# XXXX_426471_007_Secondary_PCB_Raspberry_.net
KiCad netlist of a schematic drawn in Altium Designer
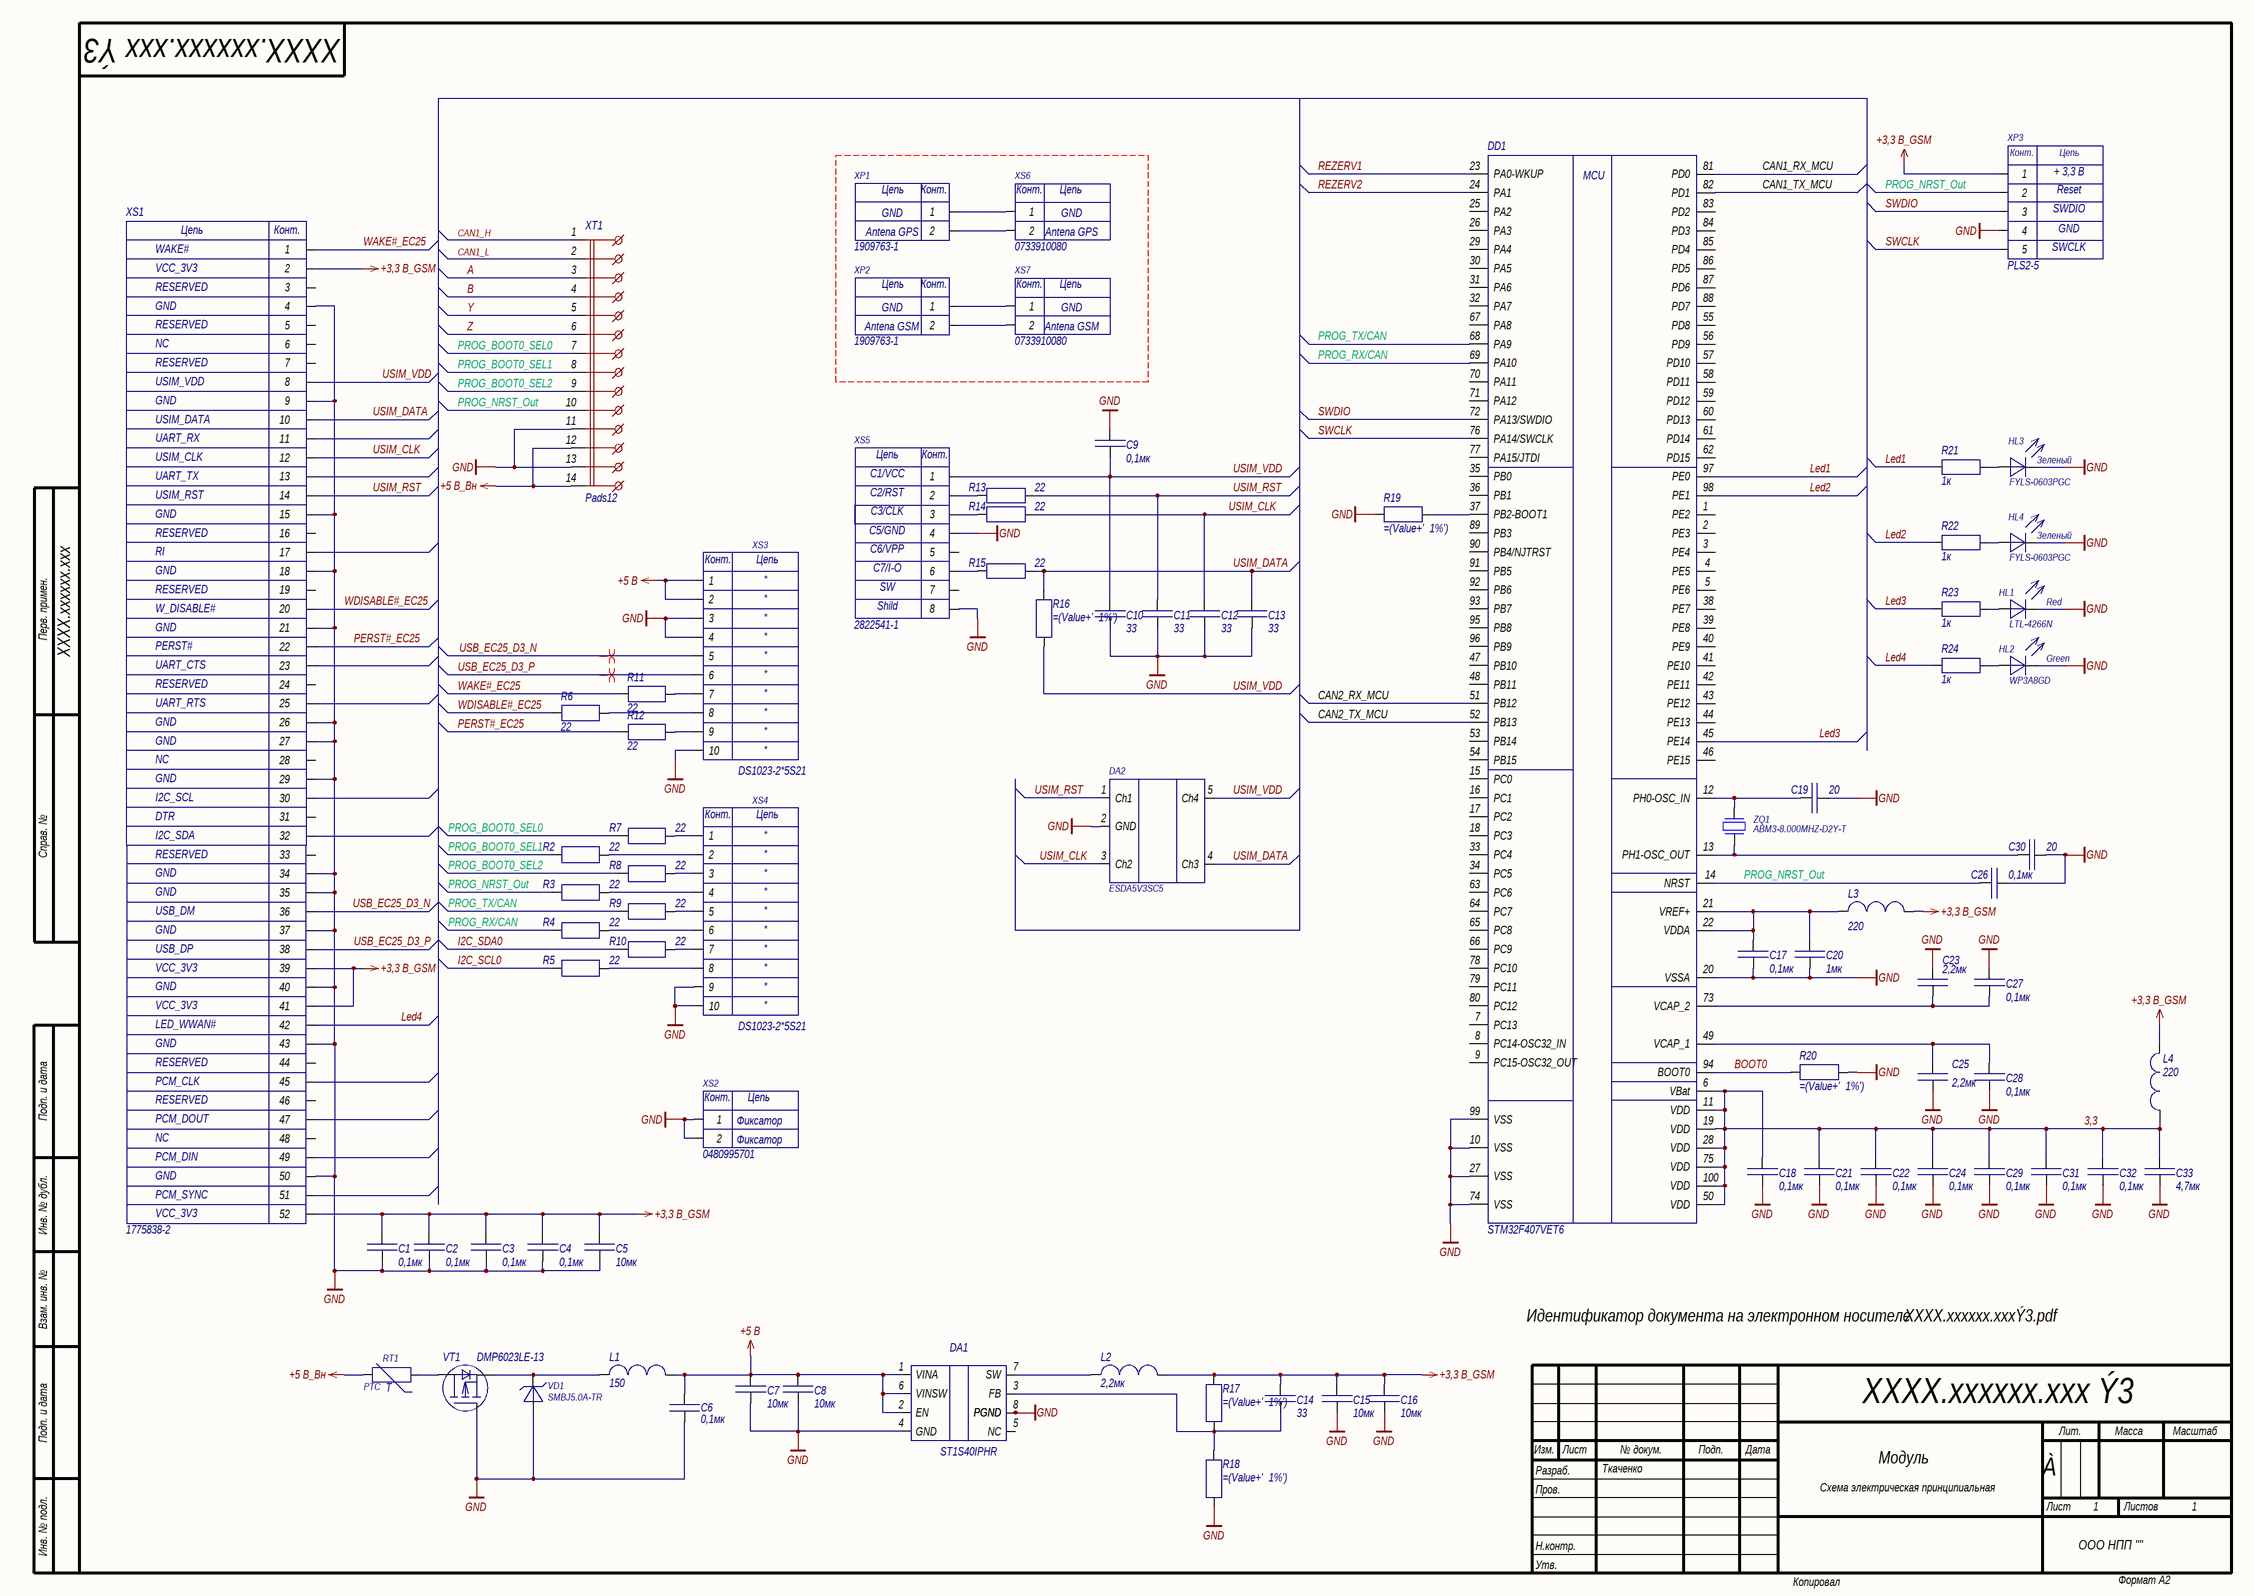
[diagram p0: XXXX.426471.007 Secondary_PCB_Raspberry_List1.SchDoc]

(export (version "E")
  (design (tool "Eeschema 10.0.6"))
  (components
    (comp (ref "C1")
      (value "0,1мк")
      (footprint "CAPC1608N_SL")
      (description "CAP CER 0.1UF 50V 10% X7R 0603")
      (fields
        (field (name "PARTNUMBER") "CC0603KRX7R9BB104_Yageo")
        (field (name "MANUFACTURER") "Yageo")
        (field (name "АВТОР") "Хоменко С.П.")
      )
      (libsource (lib "BaseContactmodul") (part "C_CER"))
    )
    (comp (ref "C2")
      (value "0,1мк")
      (footprint "CAPC1608N_SL")
      (description "CAP CER 0.1UF 50V 10% X7R 0603")
      (fields
        (field (name "PARTNUMBER") "CC0603KRX7R9BB104_Yageo")
        (field (name "MANUFACTURER") "Yageo")
        (field (name "АВТОР") "Хоменко С.П.")
      )
      (libsource (lib "BaseContactmodul") (part "C_CER"))
    )
    (comp (ref "C3")
      (value "0,1мк")
      (footprint "CAPC1608N_SL")
      (description "CAP CER 0.1UF 50V 10% X7R 0603")
      (fields
        (field (name "PARTNUMBER") "CC0603KRX7R9BB104_Yageo")
        (field (name "MANUFACTURER") "Yageo")
        (field (name "АВТОР") "Хоменко С.П.")
      )
      (libsource (lib "BaseContactmodul") (part "C_CER"))
    )
    (comp (ref "C4")
      (value "0,1мк")
      (footprint "CAPC1608N_SL")
      (description "CAP CER 0.1UF 50V 10% X7R 0603")
      (fields
        (field (name "PARTNUMBER") "CC0603KRX7R9BB104_Yageo")
        (field (name "MANUFACTURER") "Yageo")
        (field (name "АВТОР") "Хоменко С.П.")
      )
      (libsource (lib "BaseContactmodul") (part "C_CER"))
    )
    (comp (ref "C5")
      (value "10мк")
      (footprint "CAPC2012N")
      (description "CAP CER 10UF 10V 10% X7R 0805")
      (fields
        (field (name "PARTNUMBER") "GCM21BR71A106KE22L_Murata Electronics")
        (field (name "MANUFACTURER") "Murata Electronics")
        (field (name "АВТОР") "Хоменко С.П.")
      )
      (libsource (lib "BaseContactmodul") (part "C_CER"))
    )
    (comp (ref "C6")
      (value "0,1мк")
      (footprint "CAPC1608N_sl")
      (description "CAP CER 0.1UF 50V 10% X7R 0603")
      (fields
        (field (name "PARTNUMBER") "CC0603KRX7R9BB104_Yageo")
        (field (name "MANUFACTURER") "Yageo")
        (field (name "АВТОР") "Хоменко С.П.")
      )
      (libsource (lib "BaseContactmodul") (part "C_CER"))
    )
    (comp (ref "C7")
      (value "10мк")
      (footprint "CAPC2012N")
      (description "CAP CER 10UF 10V 10% X7R 0805")
      (fields
        (field (name "PARTNUMBER") "GCM21BR71A106KE22L_Murata Electronics")
        (field (name "MANUFACTURER") "Murata Electronics")
        (field (name "АВТОР") "Хоменко С.П.")
      )
      (libsource (lib "BaseContactmodul") (part "C_CER"))
    )
    (comp (ref "C8")
      (value "10мк")
      (footprint "CAPC2012N")
      (description "CAP CER 10UF 10V 10% X7R 0805")
      (fields
        (field (name "PARTNUMBER") "GCM21BR71A106KE22L_Murata Electronics")
        (field (name "MANUFACTURER") "Murata Electronics")
        (field (name "АВТОР") "Хоменко С.П.")
      )
      (libsource (lib "BaseContactmodul") (part "C_CER"))
    )
    (comp (ref "C9")
      (value "0,1мк")
      (footprint "CAPC1608N_SL")
      (description "CAP CER 0.1UF 50V 10% X7R 0603")
      (fields
        (field (name "PARTNUMBER") "CC0603KRX7R9BB104_Yageo")
        (field (name "MANUFACTURER") "Yageo")
        (field (name "АВТОР") "Хоменко С.П.")
      )
      (libsource (lib "BaseContactmodul") (part "C_CER"))
    )
    (comp (ref "C10")
      (value "33")
      (footprint "CAPC1608N_SL")
      (description "CAP CER 33PF 50V NPO 0603")
      (fields
        (field (name "PARTNUMBER") "CC0603JRNPO9BN330_Yageo")
        (field (name "MANUFACTURER") "Yageo")
        (field (name "АВТОР") "Хоменко С.П.")
      )
      (libsource (lib "BaseContactmodul") (part "C_CER"))
    )
    (comp (ref "C11")
      (value "33")
      (footprint "CAPC1608N_SL")
      (description "CAP CER 33PF 50V NPO 0603")
      (fields
        (field (name "PARTNUMBER") "CC0603JRNPO9BN330_Yageo")
        (field (name "MANUFACTURER") "Yageo")
        (field (name "АВТОР") "Хоменко С.П.")
      )
      (libsource (lib "BaseContactmodul") (part "C_CER"))
    )
    (comp (ref "C12")
      (value "33")
      (footprint "CAPC1608N_SL")
      (description "CAP CER 33PF 50V NPO 0603")
      (fields
        (field (name "PARTNUMBER") "CC0603JRNPO9BN330_Yageo")
        (field (name "MANUFACTURER") "Yageo")
        (field (name "АВТОР") "Хоменко С.П.")
      )
      (libsource (lib "BaseContactmodul") (part "C_CER"))
    )
    (comp (ref "C13")
      (value "33")
      (footprint "CAPC1608N_SL")
      (description "CAP CER 33PF 50V NPO 0603")
      (fields
        (field (name "PARTNUMBER") "CC0603JRNPO9BN330_Yageo")
        (field (name "MANUFACTURER") "Yageo")
        (field (name "АВТОР") "Хоменко С.П.")
      )
      (libsource (lib "BaseContactmodul") (part "C_CER"))
    )
    (comp (ref "C14")
      (value "33")
      (footprint "CAPC1608N_SL")
      (description "CAP CER 33PF 50V NPO 0603")
      (fields
        (field (name "PARTNUMBER") "CC0603JRNPO9BN330_Yageo")
        (field (name "MANUFACTURER") "Yageo")
        (field (name "АВТОР") "Хоменко С.П.")
      )
      (libsource (lib "BaseContactmodul") (part "C_CER"))
    )
    (comp (ref "C15")
      (value "10мк")
      (footprint "CAPC2012N")
      (description "CAP CER 10UF 10V 10% X7R 0805")
      (fields
        (field (name "PARTNUMBER") "GCM21BR71A106KE22L_Murata Electronics")
        (field (name "MANUFACTURER") "Murata Electronics")
        (field (name "АВТОР") "Хоменко С.П.")
      )
      (libsource (lib "BaseContactmodul") (part "C_CER"))
    )
    (comp (ref "C16")
      (value "10мк")
      (footprint "CAPC2012N")
      (description "CAP CER 10UF 10V 10% X7R 0805")
      (fields
        (field (name "PARTNUMBER") "GCM21BR71A106KE22L_Murata Electronics")
        (field (name "MANUFACTURER") "Murata Electronics")
        (field (name "АВТОР") "Хоменко С.П.")
      )
      (libsource (lib "BaseContactmodul") (part "C_CER"))
    )
    (comp (ref "C17")
      (value "0,1мк")
      (footprint "CAPC1608N_SL")
      (description "CAP CER 0.1UF 50V 10% X7R 0603")
      (fields
        (field (name "PARTNUMBER") "CC0603KRX7R9BB104_Yageo")
        (field (name "MANUFACTURER") "Yageo")
        (field (name "АВТОР") "Хоменко С.П.")
      )
      (libsource (lib "BaseContactmodul") (part "C_CER"))
    )
    (comp (ref "C18")
      (value "0,1мк")
      (footprint "CAPC1608N_SL")
      (description "CAP CER 0.1UF 50V 10% X7R 0603")
      (fields
        (field (name "PARTNUMBER") "CC0603KRX7R9BB104_Yageo")
        (field (name "MANUFACTURER") "Yageo")
        (field (name "АВТОР") "Хоменко С.П.")
      )
      (libsource (lib "BaseContactmodul") (part "C_CER"))
    )
    (comp (ref "C19")
      (value "20")
      (footprint "CAPC1608N_SL")
      (description "CAP CER 20PF 50V 5% NPO 0603")
      (fields
        (field (name "PARTNUMBER") "CC0603JRNPO9BN200_Yageo")
        (field (name "MANUFACTURER") "Yageo")
        (field (name "АВТОР") "Хоменко С.П.")
      )
      (libsource (lib "BaseContactmodul") (part "C_CER"))
    )
    (comp (ref "C20")
      (value "1мк")
      (footprint "CAPC1608N_SL")
      (description "CAP CER 1UF 16V 10% X7R 0603")
      (fields
        (field (name "PARTNUMBER") "CC0603KRX7R7BB105_Yageo")
        (field (name "MANUFACTURER") "Yageo")
        (field (name "АВТОР") "Хоменко С.П.")
      )
      (libsource (lib "BaseContactmodul") (part "C_CER"))
    )
    (comp (ref "C21")
      (value "0,1мк")
      (footprint "CAPC1608N_SL")
      (description "CAP CER 0.1UF 50V 10% X7R 0603")
      (fields
        (field (name "PARTNUMBER") "CC0603KRX7R9BB104_Yageo")
        (field (name "MANUFACTURER") "Yageo")
        (field (name "АВТОР") "Хоменко С.П.")
      )
      (libsource (lib "BaseContactmodul") (part "C_CER"))
    )
    (comp (ref "C22")
      (value "0,1мк")
      (footprint "CAPC1608N_SL")
      (description "CAP CER 0.1UF 50V 10% X7R 0603")
      (fields
        (field (name "PARTNUMBER") "CC0603KRX7R9BB104_Yageo")
        (field (name "MANUFACTURER") "Yageo")
        (field (name "АВТОР") "Хоменко С.П.")
      )
      (libsource (lib "BaseContactmodul") (part "C_CER"))
    )
    (comp (ref "C23")
      (value "2,2мк")
      (footprint "CAPC1608N_SL")
      (description "CAP CER 2.2UF 10V X7R 0603")
      (fields
        (field (name "PARTNUMBER") "GRM188R71A225KE15D_Murata Electronics")
        (field (name "MANUFACTURER") "Murata Electronics")
        (field (name "АВТОР") "Хоменко С.П.")
      )
      (libsource (lib "BaseContactmodul") (part "C_CER"))
    )
    (comp (ref "C24")
      (value "0,1мк")
      (footprint "CAPC1608N_SL")
      (description "CAP CER 0.1UF 50V 10% X7R 0603")
      (fields
        (field (name "PARTNUMBER") "CC0603KRX7R9BB104_Yageo")
        (field (name "MANUFACTURER") "Yageo")
        (field (name "АВТОР") "Хоменко С.П.")
      )
      (libsource (lib "BaseContactmodul") (part "C_CER"))
    )
    (comp (ref "C25")
      (value "2,2мк")
      (footprint "CAPC1608N_SL")
      (description "CAP CER 2.2UF 10V X7R 0603")
      (fields
        (field (name "PARTNUMBER") "GRM188R71A225KE15D_Murata Electronics")
        (field (name "MANUFACTURER") "Murata Electronics")
        (field (name "АВТОР") "Хоменко С.П.")
      )
      (libsource (lib "BaseContactmodul") (part "C_CER"))
    )
    (comp (ref "C26")
      (value "0,1мк")
      (footprint "CAPC1608N_SL")
      (description "CAP CER 0.1UF 50V 10% X7R 0603")
      (fields
        (field (name "PARTNUMBER") "CC0603KRX7R9BB104_Yageo")
        (field (name "MANUFACTURER") "Yageo")
        (field (name "АВТОР") "Хоменко С.П.")
      )
      (libsource (lib "BaseContactmodul") (part "C_CER"))
    )
    (comp (ref "C27")
      (value "0,1мк")
      (footprint "CAPC1608N_SL")
      (description "CAP CER 0.1UF 50V 10% X7R 0603")
      (fields
        (field (name "PARTNUMBER") "CC0603KRX7R9BB104_Yageo")
        (field (name "MANUFACTURER") "Yageo")
        (field (name "АВТОР") "Хоменко С.П.")
      )
      (libsource (lib "BaseContactmodul") (part "C_CER"))
    )
    (comp (ref "C28")
      (value "0,1мк")
      (footprint "CAPC1608N_SL")
      (description "CAP CER 0.1UF 50V 10% X7R 0603")
      (fields
        (field (name "PARTNUMBER") "CC0603KRX7R9BB104_Yageo")
        (field (name "MANUFACTURER") "Yageo")
        (field (name "АВТОР") "Хоменко С.П.")
      )
      (libsource (lib "BaseContactmodul") (part "C_CER"))
    )
    (comp (ref "C29")
      (value "0,1мк")
      (footprint "CAPC1608N_SL")
      (description "CAP CER 0.1UF 50V 10% X7R 0603")
      (fields
        (field (name "PARTNUMBER") "CC0603KRX7R9BB104_Yageo")
        (field (name "MANUFACTURER") "Yageo")
        (field (name "АВТОР") "Хоменко С.П.")
      )
      (libsource (lib "BaseContactmodul") (part "C_CER"))
    )
    (comp (ref "C30")
      (value "20")
      (footprint "CAPC1608N_SL")
      (description "CAP CER 20PF 50V 5% NPO 0603")
      (fields
        (field (name "PARTNUMBER") "CC0603JRNPO9BN200_Yageo")
        (field (name "MANUFACTURER") "Yageo")
        (field (name "АВТОР") "Хоменко С.П.")
      )
      (libsource (lib "BaseContactmodul") (part "C_CER"))
    )
    (comp (ref "C31")
      (value "0,1мк")
      (footprint "CAPC1608N_SL")
      (description "CAP CER 0.1UF 50V 10% X7R 0603")
      (fields
        (field (name "PARTNUMBER") "CC0603KRX7R9BB104_Yageo")
        (field (name "MANUFACTURER") "Yageo")
        (field (name "АВТОР") "Хоменко С.П.")
      )
      (libsource (lib "BaseContactmodul") (part "C_CER"))
    )
    (comp (ref "C32")
      (value "0,1мк")
      (footprint "CAPC1608N_SL")
      (description "CAP CER 0.1UF 50V 10% X7R 0603")
      (fields
        (field (name "PARTNUMBER") "CC0603KRX7R9BB104_Yageo")
        (field (name "MANUFACTURER") "Yageo")
        (field (name "АВТОР") "Хоменко С.П.")
      )
      (libsource (lib "BaseContactmodul") (part "C_CER"))
    )
    (comp (ref "C33")
      (value "4,7мк")
      (footprint "CAPC1608N_SL")
      (description "CAP CER 4.7UF 10V 10% X5R 0603")
      (fields
        (field (name "PARTNUMBER") "CC0603KRX5R6BB475_Yageo")
        (field (name "MANUFACTURER") "Yageo")
        (field (name "АВТОР") "Хоменко С.П.")
      )
      (libsource (lib "BaseContactmodul") (part "C_CER"))
    )
    (comp (ref "DA1")
      (value "ST1S40IPHR")
      (footprint "HSOP-8")
      (description "IC REG BUCK ADJ 3A SYNC 8-HSOP")
      (fields
        (field (name "PARTNUMBER") "ST1S40IPHR_STMicroelectronics")
        (field (name "MANUFACTURER") "STMicroelectronics")
        (field (name "АВТОР") "Ткаченко М.")
      )
      (libsource (lib "BaseContactmodul") (part "ST1S40IPHR"))
    )
    (comp (ref "DA2")
      (value "ESDA5V3SC5")
      (footprint "SOT23-5AN")
      (description "TVS DIODE 3V SOT23-5L")
      (fields
        (field (name "PARTNUMBER") "ESDA5V3SC5_STMicroelectronics")
        (field (name "MANUFACTURER") "STMicroelectronics")
        (field (name "АВТОР") "Ткаченко М.")
      )
      (libsource (lib "BaseContactmodul") (part "ESDA5V3SC5"))
    )
    (comp (ref "DD1")
      (value "STM32F407VET6")
      (footprint "LQFP100")
      (fields
        (field (name "PARTNUMBER") "STM32F407VET6_STMicroelectronics")
        (field (name "MANUFACTURER") "STMicroelectronics")
        (field (name "VOLTAGE") "3,3 В")
        (field (name "АВТОР") "Ткаченко М.")
      )
      (libsource (lib "BaseContactmodul") (part "STM32F407VET6"))
    )
    (comp (ref "HL1")
      (value "LTL-4266N")
      (footprint "Led3mm")
      (description "Red 638nm LED Indication - Discrete 1.8V Radial")
      (fields
        (field (name "NOTESCH") "Red")
        (field (name "PARTNUMBER") "LTL-4266N_LITE_ON")
        (field (name "MANUFACTURER") "LITE_ON")
        (field (name "АВТОР") "Ткаченко М.")
      )
      (libsource (lib "BaseContactmodul") (part "HL"))
    )
    (comp (ref "HL2")
      (value "WP3A8GD")
      (footprint "LED-2.5_G")
      (description "Green 568nm LED Indication - Discrete 2.2V Radial")
      (fields
        (field (name "NOTESCH") "Green")
        (field (name "PARTNUMBER") "WP3A8GD_Kingbright")
        (field (name "MANUFACTURER") "Kingbright")
        (field (name "АВТОР") "Ткаченко М.")
      )
      (libsource (lib "BaseContactmodul") (part "HL"))
    )
    (comp (ref "HL3")
      (value "FYLS-0603PGC")
      (footprint "HL0603_GREEN_SL")
      (description "Светодиод маломощный зеленный 360mcd")
      (fields
        (field (name "NOTESCH") "Зеленый")
        (field (name "PARTNUMBER") "FYLS-0603PGC_Foryard Optoelectronics")
        (field (name "MANUFACTURER") "Foryard Optoelectronics")
        (field (name "АВТОР") "Хоменко С.П.")
      )
      (libsource (lib "BaseContactmodul") (part "HL"))
    )
    (comp (ref "HL4")
      (value "FYLS-0603PGC")
      (footprint "HL0603_GREEN_SL")
      (description "Светодиод маломощный зеленный 360mcd")
      (fields
        (field (name "NOTESCH") "Зеленый")
        (field (name "PARTNUMBER") "FYLS-0603PGC_Foryard Optoelectronics")
        (field (name "MANUFACTURER") "Foryard Optoelectronics")
        (field (name "АВТОР") "Хоменко С.П.")
      )
      (libsource (lib "BaseContactmodul") (part "HL"))
    )
    (comp (ref "L1")
      (value "150")
      (footprint "INDC_56x51")
      (fields
        (field (name "PARTNUMBER") "74279224151_Wurth-Electronics-Inc")
        (field (name "MANUFACTURER") "Wurth-Electronics-Inc")
        (field (name "MANUFACTURERPARTNUMBER") "74279224151")
        (field (name "АВТОР") "Ткаченко М.")
      )
      (libsource (lib "BaseContactmodul") (part "L"))
    )
    (comp (ref "L2")
      (value "2,2мк")
      (footprint "sru1048")
      (description "FIXED IND 2.2UH 6.5A 5.3 MOHM")
      (fields
        (field (name "PARTNUMBER") "SRU1048-2R2Y_Bourns Inc.")
        (field (name "MANUFACTURER") "Bourns Inc.")
        (field (name "АВТОР") "Ткаченко М.")
      )
      (libsource (lib "BaseContactmodul") (part "L"))
    )
    (comp (ref "L3")
      (value "220")
      (footprint "L2012N")
      (description "FERRITE BEAD 220 OHM 0805 2A")
      (fields
        (field (name "PARTNUMBER") "BLM21PG221SN1D_Murata Electronics")
        (field (name "MANUFACTURER") "Murata Electronics")
        (field (name "АВТОР") "Хоменко С.П.")
      )
      (libsource (lib "BaseContactmodul") (part "L"))
    )
    (comp (ref "L4")
      (value "220")
      (footprint "L2012N")
      (description "FERRITE BEAD 220 OHM 0805 2A")
      (fields
        (field (name "PARTNUMBER") "BLM21PG221SN1D_Murata Electronics")
        (field (name "MANUFACTURER") "Murata Electronics")
        (field (name "АВТОР") "Хоменко С.П.")
      )
      (libsource (lib "BaseContactmodul") (part "L"))
    )
    (comp (ref "R2")
      (value "22")
      (footprint "RESC1608N_SL")
      (description "RES SMD 22 OHM 5% 1/10W 0603")
      (fields
        (field (name "PARTNUMBER") "RC0603JR-0722RL_Yageo")
        (field (name "MANUFACTURER") "Yageo")
        (field (name "АВТОР") "Хоменко С.П.")
      )
      (libsource (lib "BaseContactmodul") (part "R_0603"))
    )
    (comp (ref "R3")
      (value "22")
      (footprint "RESC1608N_SL")
      (description "RES SMD 22 OHM 5% 1/10W 0603")
      (fields
        (field (name "PARTNUMBER") "RC0603JR-0722RL_Yageo")
        (field (name "MANUFACTURER") "Yageo")
        (field (name "АВТОР") "Хоменко С.П.")
      )
      (libsource (lib "BaseContactmodul") (part "R_0603"))
    )
    (comp (ref "R4")
      (value "22")
      (footprint "RESC1608N_SL")
      (description "RES SMD 22 OHM 5% 1/10W 0603")
      (fields
        (field (name "PARTNUMBER") "RC0603JR-0722RL_Yageo")
        (field (name "MANUFACTURER") "Yageo")
        (field (name "АВТОР") "Хоменко С.П.")
      )
      (libsource (lib "BaseContactmodul") (part "R_0603"))
    )
    (comp (ref "R5")
      (value "22")
      (footprint "RESC1608N_SL")
      (description "RES SMD 22 OHM 5% 1/10W 0603")
      (fields
        (field (name "PARTNUMBER") "RC0603JR-0722RL_Yageo")
        (field (name "MANUFACTURER") "Yageo")
        (field (name "АВТОР") "Хоменко С.П.")
      )
      (libsource (lib "BaseContactmodul") (part "R_0603"))
    )
    (comp (ref "R6")
      (value "22")
      (footprint "RESC1608N_SL")
      (description "RES SMD 22 OHM 5% 1/10W 0603")
      (fields
        (field (name "PARTNUMBER") "RC0603JR-0722RL_Yageo")
        (field (name "MANUFACTURER") "Yageo")
        (field (name "АВТОР") "Хоменко С.П.")
      )
      (libsource (lib "BaseContactmodul") (part "R_0603"))
    )
    (comp (ref "R7")
      (value "22")
      (footprint "RESC1608N_SL")
      (description "RES SMD 22 OHM 5% 1/10W 0603")
      (fields
        (field (name "PARTNUMBER") "RC0603JR-0722RL_Yageo")
        (field (name "MANUFACTURER") "Yageo")
        (field (name "АВТОР") "Хоменко С.П.")
      )
      (libsource (lib "BaseContactmodul") (part "R_0603"))
    )
    (comp (ref "R8")
      (value "22")
      (footprint "RESC1608N_SL")
      (description "RES SMD 22 OHM 5% 1/10W 0603")
      (fields
        (field (name "PARTNUMBER") "RC0603JR-0722RL_Yageo")
        (field (name "MANUFACTURER") "Yageo")
        (field (name "АВТОР") "Хоменко С.П.")
      )
      (libsource (lib "BaseContactmodul") (part "R_0603"))
    )
    (comp (ref "R9")
      (value "22")
      (footprint "RESC1608N_SL")
      (description "RES SMD 22 OHM 5% 1/10W 0603")
      (fields
        (field (name "PARTNUMBER") "RC0603JR-0722RL_Yageo")
        (field (name "MANUFACTURER") "Yageo")
        (field (name "АВТОР") "Хоменко С.П.")
      )
      (libsource (lib "BaseContactmodul") (part "R_0603"))
    )
    (comp (ref "R10")
      (value "22")
      (footprint "RESC1608N_SL")
      (description "RES SMD 22 OHM 5% 1/10W 0603")
      (fields
        (field (name "PARTNUMBER") "RC0603JR-0722RL_Yageo")
        (field (name "MANUFACTURER") "Yageo")
        (field (name "АВТОР") "Хоменко С.П.")
      )
      (libsource (lib "BaseContactmodul") (part "R_0603"))
    )
    (comp (ref "R11")
      (value "22")
      (footprint "RESC1608N_SL")
      (description "RES SMD 22 OHM 5% 1/10W 0603")
      (fields
        (field (name "PARTNUMBER") "RC0603JR-0722RL_Yageo")
        (field (name "MANUFACTURER") "Yageo")
        (field (name "АВТОР") "Хоменко С.П.")
      )
      (libsource (lib "BaseContactmodul") (part "R_0603"))
    )
    (comp (ref "R12")
      (value "22")
      (footprint "RESC1608N_SL")
      (description "RES SMD 22 OHM 5% 1/10W 0603")
      (fields
        (field (name "PARTNUMBER") "RC0603JR-0722RL_Yageo")
        (field (name "MANUFACTURER") "Yageo")
        (field (name "АВТОР") "Хоменко С.П.")
      )
      (libsource (lib "BaseContactmodul") (part "R_0603"))
    )
    (comp (ref "R13")
      (value "22")
      (footprint "RESC1608N_SL")
      (description "RES SMD 22 OHM 5% 1/10W 0603")
      (fields
        (field (name "PARTNUMBER") "RC0603JR-0722RL_Yageo")
        (field (name "MANUFACTURER") "Yageo")
        (field (name "АВТОР") "Хоменко С.П.")
      )
      (libsource (lib "BaseContactmodul") (part "R_0603"))
    )
    (comp (ref "R14")
      (value "22")
      (footprint "RESC1608N_SL")
      (description "RES SMD 22 OHM 5% 1/10W 0603")
      (fields
        (field (name "PARTNUMBER") "RC0603JR-0722RL_Yageo")
        (field (name "MANUFACTURER") "Yageo")
        (field (name "АВТОР") "Хоменко С.П.")
      )
      (libsource (lib "BaseContactmodul") (part "R_0603"))
    )
    (comp (ref "R15")
      (value "22")
      (footprint "RESC1608N_SL")
      (description "RES SMD 22 OHM 5% 1/10W 0603")
      (fields
        (field (name "PARTNUMBER") "RC0603JR-0722RL_Yageo")
        (field (name "MANUFACTURER") "Yageo")
        (field (name "АВТОР") "Хоменко С.П.")
      )
      (libsource (lib "BaseContactmodul") (part "R_0603"))
    )
    (comp (ref "R16")
      (value "1%")
      (footprint "RESC1608N_SL")
      (description "RES SMD 15K OHM 1% 1/10W 0603")
      (fields
        (field (name "PARTNUMBER") "RC0603FR-0715KL_Yageo")
        (field (name "MANUFACTURER") "Yageo")
        (field (name "АВТОР") "Хоменко С.П.")
      )
      (libsource (lib "BaseContactmodul") (part "R_0603_1%"))
    )
    (comp (ref "R17")
      (value "1%")
      (footprint "RESC1608N_SL")
      (description "RES SMD 47K OHM 1% 1/10W 0603")
      (fields
        (field (name "PARTNUMBER") "RC0603FR-0747KL_Yageo")
        (field (name "MANUFACTURER") "Yageo")
        (field (name "АВТОР") "Ткаченко М.")
      )
      (libsource (lib "BaseContactmodul") (part "R_0603_1%"))
    )
    (comp (ref "R18")
      (value "1%")
      (footprint "RESC1608N_SL")
      (description "RES SMD 15K OHM 1% 1/10W 0603")
      (fields
        (field (name "PARTNUMBER") "RC0603FR-0715KL_Yageo")
        (field (name "MANUFACTURER") "Yageo")
        (field (name "АВТОР") "Хоменко С.П.")
      )
      (libsource (lib "BaseContactmodul") (part "R_0603_1%"))
    )
    (comp (ref "R19")
      (value "1%")
      (footprint "RESC1608N_SL")
      (description "RES SMD 15K OHM 1% 1/10W 0603")
      (fields
        (field (name "PARTNUMBER") "RC0603FR-0715KL_Yageo")
        (field (name "MANUFACTURER") "Yageo")
        (field (name "АВТОР") "Хоменко С.П.")
      )
      (libsource (lib "BaseContactmodul") (part "R_0603_1%"))
    )
    (comp (ref "R20")
      (value "1%")
      (footprint "RESC1608N_SL")
      (description "RES SMD 15K OHM 1% 1/10W 0603")
      (fields
        (field (name "PARTNUMBER") "RC0603FR-0715KL_Yageo")
        (field (name "MANUFACTURER") "Yageo")
        (field (name "АВТОР") "Хоменко С.П.")
      )
      (libsource (lib "BaseContactmodul") (part "R_0603_1%"))
    )
    (comp (ref "R21")
      (value "1к")
      (footprint "RESC1608N_SL")
      (description "RES SMD 1K OHM 5% 1/10W 0603")
      (fields
        (field (name "PARTNUMBER") "RC0603JR-071KL_Yageo")
        (field (name "MANUFACTURER") "Yageo")
        (field (name "АВТОР") "Хоменко С.П.")
      )
      (libsource (lib "BaseContactmodul") (part "R_0603"))
    )
    (comp (ref "R22")
      (value "1к")
      (footprint "RESC1608N_SL")
      (description "RES SMD 1K OHM 5% 1/10W 0603")
      (fields
        (field (name "PARTNUMBER") "RC0603JR-071KL_Yageo")
        (field (name "MANUFACTURER") "Yageo")
        (field (name "АВТОР") "Хоменко С.П.")
      )
      (libsource (lib "BaseContactmodul") (part "R_0603"))
    )
    (comp (ref "R23")
      (value "1к")
      (footprint "RESC1608N_SL")
      (description "RES SMD 1K OHM 5% 1/10W 0603")
      (fields
        (field (name "PARTNUMBER") "RC0603JR-071KL_Yageo")
        (field (name "MANUFACTURER") "Yageo")
        (field (name "АВТОР") "Хоменко С.П.")
      )
      (libsource (lib "BaseContactmodul") (part "R_0603"))
    )
    (comp (ref "R24")
      (value "1к")
      (footprint "RESC1608N_SL")
      (description "RES SMD 1K OHM 5% 1/10W 0603")
      (fields
        (field (name "PARTNUMBER") "RC0603JR-071KL_Yageo")
        (field (name "MANUFACTURER") "Yageo")
        (field (name "АВТОР") "Хоменко С.П.")
      )
      (libsource (lib "BaseContactmodul") (part "R_0603"))
    )
    (comp (ref "RT1")
      (value "PTC")
      (footprint "Fuse_2920")
      (description "PTC RESET FUSE 12V 6A 2920")
      (fields
        (field (name "PARTNUMBER") "2920L600/12MR_Littelfuse")
        (field (name "MANUFACTURER") "Littelfuse")
        (field (name "АВТОР") "Ткаченко М.")
      )
      (libsource (lib "BaseContactmodul") (part "PTC"))
    )
    (comp (ref "VD1")
      (value "SMBJ5.0A-TR")
      (footprint "DO-214AA(SMB)")
      (description "TVS DIODE 5VWM 13.4VC DO214AA")
      (fields
        (field (name "PARTNUMBER") "SMBJ5.0A-TR_STMicroelectronics")
        (field (name "MANUFACTURER") "STMicroelectronics")
        (field (name "АВТОР") "Хоменко С.П.")
      )
      (libsource (lib "BaseContactmodul") (part "VD_TVS"))
    )
    (comp (ref "VT1")
      (value "DMP6023LE-13")
      (footprint "SOT230P700X180-3M")
      (description "Транзистор P-канальный")
      (fields
        (field (name "PARTNUMBER") "DMP6023LE-13_Diodes Incorporated")
        (field (name "MANUFACTURER") "Diodes Incorporated")
        (field (name "АВТОР") "Ткаченко М.")
      )
      (libsource (lib "BaseContactmodul") (part "P_MOSFET_GSD_132"))
    )
    (comp (ref "XP1")
      (value "1909763-1")
      (footprint "1909763-1")
      (description "CONN UMCC JACK STR 50OHM SMD")
      (fields
        (field (name "NET_NAME1") "GND")
        (field (name "NET_NAME2") "Antena GPS")
        (field (name "PARTNUMBER") "1909763-1_TE Connectivity")
        (field (name "MANUFACTURER") "TE Connectivity")
        (field (name "АВТОР") "Ткаченко М.")
      )
      (libsource (lib "BaseContactmodul") (part "XP_2"))
    )
    (comp (ref "XP2")
      (value "1909763-1")
      (footprint "1909763-1")
      (description "CONN UMCC JACK STR 50OHM SMD")
      (fields
        (field (name "NET_NAME1") "GND")
        (field (name "NET_NAME2") "Antena GSM")
        (field (name "PARTNUMBER") "1909763-1_TE Connectivity")
        (field (name "MANUFACTURER") "TE Connectivity")
        (field (name "АВТОР") "Ткаченко М.")
      )
      (libsource (lib "BaseContactmodul") (part "XP_2"))
    )
    (comp (ref "XP3")
      (value "PLS2-5")
      (footprint "PLS2-5")
      (fields
        (field (name "NET_NAME1") "+ 3,3 В")
        (field (name "NET_NAME2") "Reset")
        (field (name "NET_NAME3") "SWDIO")
        (field (name "NET_NAME4") "GND")
        (field (name "NET_NAME5") "SWCLK")
        (field (name "PARTNUMBER") "PLS2-5_CONNFLY")
        (field (name "MANUFACTURER") "CONNFLY")
      )
      (libsource (lib "BaseContactmodul") (part "XP_5pin"))
    )
    (comp (ref "XS1")
      (value "1775838-2")
      (footprint "2041119-1CB")
      (description "CONN PCI EXP MINI FEMALE 52POS")
      (fields
        (field (name "NET_NAME3") "RESERVED")
        (field (name "NET_NAME4") "GND")
        (field (name "NET_NAME5") "RESERVED")
        (field (name "NET_NAME6") "NC")
        (field (name "NET_NAME7") "RESERVED")
        (field (name "NET_NAME8") "USIM_VDD")
        (field (name "NET_NAME9") "GND")
        (field (name "NET_NAME10") "USIM_DATA")
        (field (name "NET_NAME11") "UART_RX")
        (field (name "NET_NAME12") "USIM_CLK")
        (field (name "NET_NAME13") "UART_TX")
        (field (name "NET_NAME14") "USIM_RST")
        (field (name "NET_NAME15") "GND")
        (field (name "NET_NAME16") "RESERVED")
        (field (name "NET_NAME17") "RI")
        (field (name "NET_NAME18") "GND")
        (field (name "NET_NAME19") "RESERVED")
        (field (name "NET_NAME20") "W_DISABLE#")
        (field (name "NET_NAME21") "GND")
        (field (name "NET_NAME22") "PERST#")
        (field (name "NET_NAME23") "UART_CTS")
        (field (name "NET_NAME24") "RESERVED")
        (field (name "NET_NAME25") "UART_RTS")
        (field (name "NET_NAME26") "GND")
        (field (name "NET_NAME27") "GND")
        (field (name "NET_NAME28") "NC")
        (field (name "NET_NAME29") "GND")
        (field (name "NET_NAME30") "I2C_SCL")
        (field (name "NET_NAME31") "DTR")
        (field (name "NET_NAME32") "I2C_SDA")
        (field (name "NET_NAME33") "RESERVED")
        (field (name "NET_NAME34") "GND")
        (field (name "NET_NAME35") "GND")
        (field (name "NET_NAME36") "USB_DM")
        (field (name "NET_NAME37") "GND")
        (field (name "NET_NAME38") "USB_DP")
        (field (name "NET_NAME39") "VCC_3V3")
        (field (name "NET_NAME40") "GND")
        (field (name "NET_NAME1") "WAKE#")
        (field (name "NET_NAME2") "VCC_3V3")
        (field (name "NET_NAME41") "VCC_3V3")
        (field (name "NET_NAME42") "LED_WWAN#")
        (field (name "NET_NAME43") "GND")
        (field (name "NET_NAME44") "RESERVED")
        (field (name "NET_NAME45") "PCM_CLK")
        (field (name "NET_NAME46") "RESERVED")
        (field (name "NET_NAME47") "PCM_DOUT")
        (field (name "NET_NAME48") "NC")
        (field (name "NET_NAME49") "PCM_DIN")
        (field (name "NET_NAME50") "GND")
        (field (name "NET_NAME51") "PCM_SYNC")
        (field (name "NET_NAME52") "VCC_3V3")
        (field (name "PARTNUMBER") "1775838-2_TE Connectivity")
        (field (name "MANUFACTURER") "TE Connectivity")
        (field (name "АВТОР") "Ткаченко М.")
      )
      (libsource (lib "BaseContactmodul") (part "XS_52pin_MPCI_ex"))
    )
    (comp (ref "XS2")
      (value "0480995701")
      (footprint "NoPackage")
      (description "Connector Latch For PCI Express Mini Card")
      (fields
        (field (name "NET_NAME1") "Фиксатор")
        (field (name "NET_NAME2") "Фиксатор")
        (field (name "PARTNUMBER") "0480995701_Molex")
        (field (name "MANUFACTURER") "Molex")
        (field (name "АВТОР") "Ткаченко М.")
      )
      (libsource (lib "BaseContactmodul") (part "XS_2"))
    )
    (comp (ref "XS3")
      (value "DS1023-2*5S21")
      (footprint "pbD-10")
      (fields
        (field (name "NET_NAME1") "*")
        (field (name "NET_NAME2") "*")
        (field (name "NET_NAME3") "*")
        (field (name "NET_NAME4") "*")
        (field (name "NET_NAME5") "*")
        (field (name "NET_NAME6") "*")
        (field (name "NET_NAME7") "*")
        (field (name "NET_NAME8") "*")
        (field (name "NET_NAME9") "*")
        (field (name "NET_NAME10") "*")
        (field (name "PARTNUMBER") "DS1023-2*5S21_CONNFLY")
        (field (name "MANUFACTURER") "CONNFLY")
      )
      (libsource (lib "BaseContactmodul") (part "XS_10pin"))
    )
    (comp (ref "XS4")
      (value "DS1023-2*5S21")
      (footprint "pbD-10")
      (fields
        (field (name "NET_NAME1") "*")
        (field (name "NET_NAME2") "*")
        (field (name "NET_NAME3") "*")
        (field (name "NET_NAME4") "*")
        (field (name "NET_NAME5") "*")
        (field (name "NET_NAME6") "*")
        (field (name "NET_NAME7") "*")
        (field (name "NET_NAME8") "*")
        (field (name "NET_NAME9") "*")
        (field (name "NET_NAME10") "*")
        (field (name "PARTNUMBER") "DS1023-2*5S21_CONNFLY")
        (field (name "MANUFACTURER") "CONNFLY")
      )
      (libsource (lib "BaseContactmodul") (part "XS_10pin"))
    )
    (comp (ref "XS5")
      (value "2822541-1")
      (footprint "2822541-1_MSIM")
      (description "7 (6 + 1) Position Card Connector Micro SIM Surface Mount, Right Angle Gold")
      (fields
        (field (name "NET_NAME1") "C1/VCC")
        (field (name "NET_NAME2") "C2/RST")
        (field (name "NET_NAME3") "C3/CLK")
        (field (name "NET_NAME4") "C5/GND")
        (field (name "NET_NAME5") "C6/VPP")
        (field (name "NET_NAME6") "C7/I-O")
        (field (name "NET_NAME7") "SW")
        (field (name "NET_NAME8") "Shild")
        (field (name "PARTNUMBER") "2822541-1_TE Connectivity")
        (field (name "MANUFACTURER") "TE Connectivity")
        (field (name "АВТОР") "Ткаченко М.")
      )
      (libsource (lib "BaseContactmodul") (part "XS_8pin"))
    )
    (comp (ref "XS6")
      (value "0733910080")
      (footprint "0733910080")
      (description "SMA Connector Jack, Female Socket 50 Ohm Through Hole, Right Angle Solder")
      (fields
        (field (name "NET_NAME1") "GND")
        (field (name "NET_NAME2") "Antena GPS")
        (field (name "PARTNUMBER") "0733910080_Molex")
        (field (name "MANUFACTURER") "Molex")
        (field (name "АВТОР") "Ткаченко М.")
      )
      (libsource (lib "BaseContactmodul") (part "XS_2"))
    )
    (comp (ref "XS7")
      (value "0733910080")
      (footprint "0733910080")
      (description "SMA Connector Jack, Female Socket 50 Ohm Through Hole, Right Angle Solder")
      (fields
        (field (name "NET_NAME1") "GND")
        (field (name "NET_NAME2") "Antena GSM")
        (field (name "PARTNUMBER") "0733910080_Molex")
        (field (name "MANUFACTURER") "Molex")
        (field (name "АВТОР") "Ткаченко М.")
      )
      (libsource (lib "BaseContactmodul") (part "XS_2"))
    )
    (comp (ref "XT1")
      (value "Pads12")
      (footprint "pads12")
      (fields
        (field (name "PARTNUMBER") "pads12_Контактмодуль")
        (field (name "MANUFACTURERPARTNUMBER") "pads12")
        (field (name "MANUFACTURER") "Контактмодуль")
        (field (name "АВТОР") "Ткаченко М.")
      )
      (libsource (lib "BaseContactmodul") (part "Pads12"))
    )
    (comp (ref "ZQ1")
      (value "ABM3-8.000MHZ-D2Y-T")
      (footprint "ABM3")
      (description "8MHz ±20ppm Crystal 18pF 140 Ohm -40°C ~ 85°C Surface Mount 2-SMD")
      (fields
        (field (name "PARTNUMBER") "ABM3-8.000MHZ-D2Y-T_Abracon LLC")
        (field (name "MANUFACTURER") "Abracon LLC")
        (field (name "АВТОР") "Хоменко С.П.")
      )
      (libsource (lib "BaseContactmodul") (part "XTAL"))
    )
  )
  (nets
    (net (code "1") (name "+3,3 В_GSM") (class "Default")
      (node (ref "C1") (pin "1") (pintype "passive"))
      (node (ref "C14") (pin "1") (pintype "passive"))
      (node (ref "C15") (pin "1") (pintype "passive"))
      (node (ref "C16") (pin "1") (pintype "passive"))
      (node (ref "C2") (pin "1") (pintype "passive"))
      (node (ref "C3") (pin "1") (pintype "passive"))
      (node (ref "C4") (pin "1") (pintype "passive"))
      (node (ref "C5") (pin "1") (pintype "passive"))
      (node (ref "L2") (pin "2") (pinfunction "2_2") (pintype "passive"))
      (node (ref "L3") (pin "2") (pinfunction "2_2") (pintype "passive"))
      (node (ref "L4") (pin "2") (pinfunction "2_2") (pintype "passive"))
      (node (ref "R17") (pin "2") (pinfunction "2_2") (pintype "passive"))
      (node (ref "XP3") (pin "1") (pinfunction "1_1") (pintype "passive"))
      (node (ref "XS1") (pin "2") (pinfunction "2_2") (pintype "passive"))
      (node (ref "XS1") (pin "39") (pinfunction "39_39") (pintype "passive"))
      (node (ref "XS1") (pin "41") (pinfunction "41_41") (pintype "passive"))
      (node (ref "XS1") (pin "52") (pinfunction "52_52") (pintype "passive"))
    )
    (net (code "2") (name "+5 В") (class "Default")
      (node (ref "C6") (pin "1") (pintype "passive"))
      (node (ref "C7") (pin "1") (pintype "passive"))
      (node (ref "C8") (pin "1") (pintype "passive"))
      (node (ref "DA1") (pin "1") (pinfunction "VINA_1") (pintype "power_in"))
      (node (ref "DA1") (pin "2") (pinfunction "EN_2") (pintype "passive"))
      (node (ref "DA1") (pin "6") (pinfunction "VINSW_6") (pintype "passive"))
      (node (ref "L1") (pin "2") (pinfunction "2_2") (pintype "passive"))
      (node (ref "XS3") (pin "1") (pinfunction "1_1") (pintype "passive"))
      (node (ref "XS3") (pin "2") (pinfunction "2_2") (pintype "passive"))
    )
    (net (code "3") (name "+5 В_Вн") (class "Default")
      (node (ref "RT1") (pin "1") (pinfunction "1_1") (pintype "passive"))
      (node (ref "XT1") (pin "12") (pinfunction "12_12") (pintype "passive"))
      (node (ref "XT1") (pin "14") (pinfunction "14_14") (pintype "passive"))
    )
    (net (code "4") (name "/3,3") (class "Default")
      (node (ref "C18") (pin "1") (pintype "passive"))
      (node (ref "C21") (pin "1") (pintype "passive"))
      (node (ref "C22") (pin "1") (pintype "passive"))
      (node (ref "C24") (pin "1") (pintype "passive"))
      (node (ref "C29") (pin "1") (pintype "passive"))
      (node (ref "C31") (pin "1") (pintype "passive"))
      (node (ref "C32") (pin "1") (pintype "passive"))
      (node (ref "C33") (pin "1") (pintype "passive"))
      (node (ref "DD1") (pin "100") (pinfunction "VDD_100") (pintype "passive"))
      (node (ref "DD1") (pin "11") (pinfunction "VDD_11") (pintype "passive"))
      (node (ref "DD1") (pin "19") (pinfunction "VDD_19") (pintype "passive"))
      (node (ref "DD1") (pin "28") (pinfunction "VDD_28") (pintype "passive"))
      (node (ref "DD1") (pin "50") (pinfunction "VDD_50") (pintype "passive"))
      (node (ref "DD1") (pin "6") (pinfunction "VBat_6") (pintype "passive"))
      (node (ref "DD1") (pin "75") (pinfunction "VDD_75") (pintype "passive"))
      (node (ref "L4") (pin "1") (pinfunction "1_1") (pintype "passive"))
    )
    (net (code "5") (name "/A") (class "Default")
      (node (ref "XT1") (pin "3") (pinfunction "3_3") (pintype "passive"))
    )
    (net (code "6") (name "/B") (class "Default")
      (node (ref "XT1") (pin "4") (pinfunction "4_4") (pintype "passive"))
    )
    (net (code "7") (name "/BOOT0") (class "Default")
      (node (ref "DD1") (pin "94") (pinfunction "BOOT0_94") (pintype "passive"))
      (node (ref "R20") (pin "1") (pinfunction "1_1") (pintype "passive"))
    )
    (net (code "8") (name "/CAN1_H") (class "Default")
      (node (ref "XT1") (pin "1") (pinfunction "1_1") (pintype "passive"))
    )
    (net (code "9") (name "/CAN1_L") (class "Default")
      (node (ref "XT1") (pin "2") (pinfunction "2_2") (pintype "passive"))
    )
    (net (code "10") (name "/CAN1_RX_MCU") (class "Default")
      (node (ref "DD1") (pin "81") (pinfunction "PD0_81") (pintype "passive"))
    )
    (net (code "11") (name "/CAN1_TX_MCU") (class "Default")
      (node (ref "DD1") (pin "82") (pinfunction "PD1_82") (pintype "passive"))
    )
    (net (code "12") (name "/CAN2_RX_MCU") (class "Default")
      (node (ref "DD1") (pin "51") (pinfunction "PB12_51") (pintype "passive"))
    )
    (net (code "13") (name "/CAN2_TX_MCU") (class "Default")
      (node (ref "DD1") (pin "52") (pinfunction "PB13_52") (pintype "passive"))
    )
    (net (code "14") (name "/I2C_SCL0") (class "Default")
      (node (ref "R5") (pin "2") (pinfunction "2_2") (pintype "passive"))
    )
    (net (code "15") (name "/I2C_SDA0") (class "Default")
      (node (ref "R10") (pin "2") (pinfunction "2_2") (pintype "passive"))
    )
    (net (code "16") (name "/Led1") (class "Default")
      (node (ref "DD1") (pin "97") (pinfunction "PE0_97") (pintype "passive"))
      (node (ref "R21") (pin "1") (pinfunction "1_1") (pintype "passive"))
    )
    (net (code "17") (name "/Led2") (class "Default")
      (node (ref "DD1") (pin "98") (pinfunction "PE1_98") (pintype "passive"))
      (node (ref "R22") (pin "1") (pinfunction "1_1") (pintype "passive"))
    )
    (net (code "18") (name "/Led3") (class "Default")
      (node (ref "DD1") (pin "45") (pinfunction "PE14_45") (pintype "passive"))
      (node (ref "R23") (pin "1") (pinfunction "1_1") (pintype "passive"))
    )
    (net (code "19") (name "/Led4") (class "Default")
      (node (ref "R24") (pin "1") (pinfunction "1_1") (pintype "passive"))
      (node (ref "XS1") (pin "42") (pinfunction "42_42") (pintype "passive"))
    )
    (net (code "20") (name "/PERST#_EC25") (class "Default")
      (node (ref "R12") (pin "2") (pinfunction "2_2") (pintype "passive"))
      (node (ref "XS1") (pin "22") (pinfunction "22_22") (pintype "passive"))
    )
    (net (code "21") (name "/PROG_BOOT0_SEL0") (class "Default")
      (node (ref "R7") (pin "2") (pinfunction "2_2") (pintype "passive"))
      (node (ref "XT1") (pin "7") (pinfunction "7_7") (pintype "passive"))
    )
    (net (code "22") (name "/PROG_BOOT0_SEL1") (class "Default")
      (node (ref "R2") (pin "2") (pinfunction "2_2") (pintype "passive"))
      (node (ref "XT1") (pin "8") (pinfunction "8_8") (pintype "passive"))
    )
    (net (code "23") (name "/PROG_BOOT0_SEL2") (class "Default")
      (node (ref "R8") (pin "2") (pinfunction "2_2") (pintype "passive"))
      (node (ref "XT1") (pin "9") (pinfunction "9_9") (pintype "passive"))
    )
    (net (code "24") (name "/PROG_NRST_Out") (class "Default")
      (node (ref "C26") (pin "2") (pintype "passive"))
      (node (ref "DD1") (pin "14") (pinfunction "NRST_14") (pintype "passive"))
      (node (ref "R3") (pin "2") (pinfunction "2_2") (pintype "passive"))
      (node (ref "XP3") (pin "2") (pinfunction "2_2") (pintype "passive"))
      (node (ref "XT1") (pin "10") (pinfunction "10_10") (pintype "passive"))
    )
    (net (code "25") (name "/PROG_RX{slash}CAN") (class "Default")
      (node (ref "DD1") (pin "69") (pinfunction "PA10_69") (pintype "passive"))
      (node (ref "R4") (pin "2") (pinfunction "2_2") (pintype "passive"))
    )
    (net (code "26") (name "/PROG_TX{slash}CAN") (class "Default")
      (node (ref "DD1") (pin "68") (pinfunction "PA9_68") (pintype "passive"))
      (node (ref "R9") (pin "2") (pinfunction "2_2") (pintype "passive"))
    )
    (net (code "27") (name "/REZERV1") (class "Default")
      (node (ref "DD1") (pin "23") (pinfunction "PA0-WKUP_23") (pintype "passive"))
    )
    (net (code "28") (name "/REZERV2") (class "Default")
      (node (ref "DD1") (pin "24") (pinfunction "PA1_24") (pintype "passive"))
    )
    (net (code "29") (name "/SWCLK") (class "Default")
      (node (ref "DD1") (pin "76") (pinfunction "PA14/SWCLK_76") (pintype "passive"))
      (node (ref "XP3") (pin "5") (pinfunction "5_5") (pintype "passive"))
    )
    (net (code "30") (name "/SWDIO") (class "Default")
      (node (ref "DD1") (pin "72") (pinfunction "PA13/SWDIO_72") (pintype "passive"))
      (node (ref "XP3") (pin "3") (pinfunction "3_3") (pintype "passive"))
    )
    (net (code "31") (name "/USB_EC25_D3_N") (class "Default")
      (node (ref "XS1") (pin "36") (pinfunction "36_36") (pintype "passive"))
      (node (ref "XS3") (pin "5") (pinfunction "5_5") (pintype "passive"))
    )
    (net (code "32") (name "/USB_EC25_D3_P") (class "Default")
      (node (ref "XS1") (pin "38") (pinfunction "38_38") (pintype "passive"))
      (node (ref "XS3") (pin "6") (pinfunction "6_6") (pintype "passive"))
    )
    (net (code "33") (name "/USIM_CLK") (class "Default")
      (node (ref "C12") (pin "1") (pintype "passive"))
      (node (ref "DA2") (pin "3") (pinfunction "Ch2_3") (pintype "passive"))
      (node (ref "R14") (pin "2") (pinfunction "2_2") (pintype "passive"))
      (node (ref "XS1") (pin "12") (pinfunction "12_12") (pintype "passive"))
    )
    (net (code "34") (name "/USIM_DATA") (class "Default")
      (node (ref "C13") (pin "1") (pintype "passive"))
      (node (ref "DA2") (pin "4") (pinfunction "Ch3_4") (pintype "passive"))
      (node (ref "R15") (pin "2") (pinfunction "2_2") (pintype "passive"))
      (node (ref "R16") (pin "2") (pinfunction "2_2") (pintype "passive"))
      (node (ref "XS1") (pin "10") (pinfunction "10_10") (pintype "passive"))
    )
    (net (code "35") (name "/USIM_RST") (class "Default")
      (node (ref "C11") (pin "1") (pintype "passive"))
      (node (ref "DA2") (pin "1") (pinfunction "Ch1_1") (pintype "passive"))
      (node (ref "R13") (pin "2") (pinfunction "2_2") (pintype "passive"))
      (node (ref "XS1") (pin "14") (pinfunction "14_14") (pintype "passive"))
    )
    (net (code "36") (name "/USIM_VDD") (class "Default")
      (node (ref "C10") (pin "1") (pintype "passive"))
      (node (ref "C9") (pin "1") (pintype "passive"))
      (node (ref "DA2") (pin "5") (pinfunction "Ch4_5") (pintype "passive"))
      (node (ref "R16") (pin "1") (pinfunction "1_1") (pintype "passive"))
      (node (ref "XS1") (pin "8") (pinfunction "8_8") (pintype "passive"))
      (node (ref "XS5") (pin "1") (pinfunction "1_1") (pintype "passive"))
    )
    (net (code "37") (name "/WAKE#_EC25") (class "Default")
      (node (ref "R11") (pin "2") (pinfunction "2_2") (pintype "passive"))
      (node (ref "XS1") (pin "1") (pinfunction "1_1") (pintype "passive"))
    )
    (net (code "38") (name "/WDISABLE#_EC25") (class "Default")
      (node (ref "R6") (pin "2") (pinfunction "2_2") (pintype "passive"))
      (node (ref "XS1") (pin "20") (pinfunction "20_20") (pintype "passive"))
    )
    (net (code "39") (name "/Y") (class "Default")
      (node (ref "XT1") (pin "5") (pinfunction "5_5") (pintype "passive"))
    )
    (net (code "40") (name "/Z") (class "Default")
      (node (ref "XT1") (pin "6") (pinfunction "6_6") (pintype "passive"))
    )
    (net (code "41") (name "GND") (class "Default")
      (node (ref "C1") (pin "2") (pintype "passive"))
      (node (ref "C10") (pin "2") (pintype "passive"))
      (node (ref "C11") (pin "2") (pintype "passive"))
      (node (ref "C12") (pin "2") (pintype "passive"))
      (node (ref "C13") (pin "2") (pintype "passive"))
      (node (ref "C15") (pin "2") (pintype "passive"))
      (node (ref "C16") (pin "2") (pintype "passive"))
      (node (ref "C17") (pin "2") (pintype "passive"))
      (node (ref "C18") (pin "2") (pintype "passive"))
      (node (ref "C19") (pin "1") (pintype "passive"))
      (node (ref "C2") (pin "2") (pintype "passive"))
      (node (ref "C20") (pin "2") (pintype "passive"))
      (node (ref "C21") (pin "2") (pintype "passive"))
      (node (ref "C22") (pin "2") (pintype "passive"))
      (node (ref "C23") (pin "2") (pintype "passive"))
      (node (ref "C24") (pin "2") (pintype "passive"))
      (node (ref "C25") (pin "1") (pintype "passive"))
      (node (ref "C26") (pin "1") (pintype "passive"))
      (node (ref "C27") (pin "1") (pintype "passive"))
      (node (ref "C28") (pin "2") (pintype "passive"))
      (node (ref "C29") (pin "2") (pintype "passive"))
      (node (ref "C3") (pin "2") (pintype "passive"))
      (node (ref "C30") (pin "1") (pintype "passive"))
      (node (ref "C31") (pin "2") (pintype "passive"))
      (node (ref "C32") (pin "2") (pintype "passive"))
      (node (ref "C33") (pin "2") (pintype "passive"))
      (node (ref "C4") (pin "2") (pintype "passive"))
      (node (ref "C5") (pin "2") (pintype "passive"))
      (node (ref "C6") (pin "2") (pintype "passive"))
      (node (ref "C7") (pin "2") (pintype "passive"))
      (node (ref "C8") (pin "2") (pintype "passive"))
      (node (ref "C9") (pin "2") (pintype "passive"))
      (node (ref "DA1") (pin "4") (pinfunction "GND_4") (pintype "passive"))
      (node (ref "DA1") (pin "8") (pinfunction "PGND_8") (pintype "power_in"))
      (node (ref "DA1") (pin "9") (pinfunction "PGND_9") (pintype "power_in"))
      (node (ref "DA2") (pin "2") (pinfunction "GND_2") (pintype "passive"))
      (node (ref "DD1") (pin "10") (pinfunction "VSS_10") (pintype "passive"))
      (node (ref "DD1") (pin "20") (pinfunction "VSSA_20") (pintype "passive"))
      (node (ref "DD1") (pin "27") (pinfunction "VSS_27") (pintype "passive"))
      (node (ref "DD1") (pin "74") (pinfunction "VSS_74") (pintype "passive"))
      (node (ref "DD1") (pin "99") (pinfunction "VSS_99") (pintype "passive"))
      (node (ref "HL1") (pin "1") (pinfunction "1_1") (pintype "passive"))
      (node (ref "HL2") (pin "1") (pinfunction "1_1") (pintype "passive"))
      (node (ref "HL3") (pin "1") (pinfunction "1_1") (pintype "passive"))
      (node (ref "HL4") (pin "1") (pinfunction "1_1") (pintype "passive"))
      (node (ref "R18") (pin "1") (pinfunction "1_1") (pintype "passive"))
      (node (ref "R19") (pin "1") (pinfunction "1_1") (pintype "passive"))
      (node (ref "R20") (pin "2") (pinfunction "2_2") (pintype "passive"))
      (node (ref "VD1") (pin "2") (pinfunction "A_2") (pintype "passive"))
      (node (ref "VT1") (pin "1") (pinfunction "G_1") (pintype "passive"))
      (node (ref "XP3") (pin "4") (pinfunction "4_4") (pintype "passive"))
      (node (ref "XS1") (pin "15") (pinfunction "15_15") (pintype "passive"))
      (node (ref "XS1") (pin "18") (pinfunction "18_18") (pintype "passive"))
      (node (ref "XS1") (pin "21") (pinfunction "21_21") (pintype "passive"))
      (node (ref "XS1") (pin "26") (pinfunction "26_26") (pintype "passive"))
      (node (ref "XS1") (pin "27") (pinfunction "27_27") (pintype "passive"))
      (node (ref "XS1") (pin "29") (pinfunction "29_29") (pintype "passive"))
      (node (ref "XS1") (pin "34") (pinfunction "34_34") (pintype "passive"))
      (node (ref "XS1") (pin "35") (pinfunction "35_35") (pintype "passive"))
      (node (ref "XS1") (pin "37") (pinfunction "37_37") (pintype "passive"))
      (node (ref "XS1") (pin "4") (pinfunction "4_4") (pintype "passive"))
      (node (ref "XS1") (pin "40") (pinfunction "40_40") (pintype "passive"))
      (node (ref "XS1") (pin "43") (pinfunction "43_43") (pintype "passive"))
      (node (ref "XS1") (pin "50") (pinfunction "50_50") (pintype "passive"))
      (node (ref "XS1") (pin "9") (pinfunction "9_9") (pintype "passive"))
      (node (ref "XS2") (pin "1") (pinfunction "1_1") (pintype "passive"))
      (node (ref "XS2") (pin "2") (pinfunction "2_2") (pintype "passive"))
      (node (ref "XS3") (pin "10") (pinfunction "10_10") (pintype "passive"))
      (node (ref "XS3") (pin "3") (pinfunction "3_3") (pintype "passive"))
      (node (ref "XS3") (pin "4") (pinfunction "4_4") (pintype "passive"))
      (node (ref "XS4") (pin "10") (pinfunction "10_10") (pintype "passive"))
      (node (ref "XS4") (pin "9") (pinfunction "9_9") (pintype "passive"))
      (node (ref "XS5") (pin "4") (pinfunction "4_4") (pintype "passive"))
      (node (ref "XS5") (pin "8") (pinfunction "8_8") (pintype "passive"))
      (node (ref "XT1") (pin "11") (pinfunction "11_11") (pintype "passive"))
      (node (ref "XT1") (pin "13") (pinfunction "13_13") (pintype "passive"))
    )
    (net (code "42") (name "Net-(DA1-FB)") (class "Default")
      (node (ref "C14") (pin "2") (pintype "passive"))
      (node (ref "DA1") (pin "3") (pinfunction "FB_3") (pintype "passive"))
      (node (ref "R17") (pin "1") (pinfunction "1_1") (pintype "passive"))
      (node (ref "R18") (pin "2") (pinfunction "2_2") (pintype "passive"))
    )
    (net (code "43") (name "Net-(DA1-SW)") (class "Default")
      (node (ref "DA1") (pin "7") (pinfunction "SW_7") (pintype "power_in"))
      (node (ref "L2") (pin "1") (pinfunction "1_1") (pintype "passive"))
    )
    (net (code "44") (name "Net-(DD1-PB2-BOOT1)") (class "Default")
      (node (ref "DD1") (pin "37") (pinfunction "PB2-BOOT1_37") (pintype "passive"))
      (node (ref "R19") (pin "2") (pinfunction "2_2") (pintype "passive"))
    )
    (net (code "45") (name "Net-(DD1-PH0-OSC_IN)") (class "Default")
      (node (ref "C19") (pin "2") (pintype "passive"))
      (node (ref "DD1") (pin "12") (pinfunction "PH0-OSC_IN_12") (pintype "passive"))
      (node (ref "ZQ1") (pin "2") (pinfunction "2_2") (pintype "passive"))
    )
    (net (code "46") (name "Net-(DD1-PH1-OSC_OUT)") (class "Default")
      (node (ref "C30") (pin "2") (pintype "passive"))
      (node (ref "DD1") (pin "13") (pinfunction "PH1-OSC_OUT_13") (pintype "passive"))
      (node (ref "ZQ1") (pin "1") (pinfunction "1_1") (pintype "passive"))
    )
    (net (code "47") (name "Net-(DD1-VCAP_1)") (class "Default")
      (node (ref "C25") (pin "2") (pintype "passive"))
      (node (ref "C28") (pin "1") (pintype "passive"))
      (node (ref "DD1") (pin "49") (pinfunction "VCAP_1_49") (pintype "passive"))
    )
    (net (code "48") (name "Net-(DD1-VCAP_2)") (class "Default")
      (node (ref "C23") (pin "1") (pintype "passive"))
      (node (ref "C27") (pin "2") (pintype "passive"))
      (node (ref "DD1") (pin "73") (pinfunction "VCAP_2_73") (pintype "passive"))
    )
    (net (code "49") (name "Net-(DD1-VDDA)") (class "Default")
      (node (ref "C17") (pin "1") (pintype "passive"))
      (node (ref "C20") (pin "1") (pintype "passive"))
      (node (ref "DD1") (pin "21") (pinfunction "VREF+_21") (pintype "passive"))
      (node (ref "DD1") (pin "22") (pinfunction "VDDA_22") (pintype "passive"))
      (node (ref "L3") (pin "1") (pinfunction "1_1") (pintype "passive"))
    )
    (net (code "50") (name "Net-(HL1-Pad2)") (class "Default")
      (node (ref "HL1") (pin "2") (pinfunction "2_2") (pintype "passive"))
      (node (ref "R23") (pin "2") (pinfunction "2_2") (pintype "passive"))
    )
    (net (code "51") (name "Net-(HL2-Pad2)") (class "Default")
      (node (ref "HL2") (pin "2") (pinfunction "2_2") (pintype "passive"))
      (node (ref "R24") (pin "2") (pinfunction "2_2") (pintype "passive"))
    )
    (net (code "52") (name "Net-(HL3-Pad2)") (class "Default")
      (node (ref "HL3") (pin "2") (pinfunction "2_2") (pintype "passive"))
      (node (ref "R21") (pin "2") (pinfunction "2_2") (pintype "passive"))
    )
    (net (code "53") (name "Net-(HL4-Pad2)") (class "Default")
      (node (ref "HL4") (pin "2") (pinfunction "2_2") (pintype "passive"))
      (node (ref "R22") (pin "2") (pinfunction "2_2") (pintype "passive"))
    )
    (net (code "54") (name "Net-(R2-Pad1)") (class "Default")
      (node (ref "R2") (pin "1") (pinfunction "1_1") (pintype "passive"))
      (node (ref "XS4") (pin "2") (pinfunction "2_2") (pintype "passive"))
    )
    (net (code "55") (name "Net-(R3-Pad1)") (class "Default")
      (node (ref "R3") (pin "1") (pinfunction "1_1") (pintype "passive"))
      (node (ref "XS4") (pin "4") (pinfunction "4_4") (pintype "passive"))
    )
    (net (code "56") (name "Net-(R4-Pad1)") (class "Default")
      (node (ref "R4") (pin "1") (pinfunction "1_1") (pintype "passive"))
      (node (ref "XS4") (pin "6") (pinfunction "6_6") (pintype "passive"))
    )
    (net (code "57") (name "Net-(R5-Pad1)") (class "Default")
      (node (ref "R5") (pin "1") (pinfunction "1_1") (pintype "passive"))
      (node (ref "XS4") (pin "8") (pinfunction "8_8") (pintype "passive"))
    )
    (net (code "58") (name "Net-(R6-Pad1)") (class "Default")
      (node (ref "R6") (pin "1") (pinfunction "1_1") (pintype "passive"))
      (node (ref "XS3") (pin "8") (pinfunction "8_8") (pintype "passive"))
    )
    (net (code "59") (name "Net-(R7-Pad1)") (class "Default")
      (node (ref "R7") (pin "1") (pinfunction "1_1") (pintype "passive"))
      (node (ref "XS4") (pin "1") (pinfunction "1_1") (pintype "passive"))
    )
    (net (code "60") (name "Net-(R8-Pad1)") (class "Default")
      (node (ref "R8") (pin "1") (pinfunction "1_1") (pintype "passive"))
      (node (ref "XS4") (pin "3") (pinfunction "3_3") (pintype "passive"))
    )
    (net (code "61") (name "Net-(R9-Pad1)") (class "Default")
      (node (ref "R9") (pin "1") (pinfunction "1_1") (pintype "passive"))
      (node (ref "XS4") (pin "5") (pinfunction "5_5") (pintype "passive"))
    )
    (net (code "62") (name "Net-(R10-Pad1)") (class "Default")
      (node (ref "R10") (pin "1") (pinfunction "1_1") (pintype "passive"))
      (node (ref "XS4") (pin "7") (pinfunction "7_7") (pintype "passive"))
    )
    (net (code "63") (name "Net-(R11-Pad1)") (class "Default")
      (node (ref "R11") (pin "1") (pinfunction "1_1") (pintype "passive"))
      (node (ref "XS3") (pin "7") (pinfunction "7_7") (pintype "passive"))
    )
    (net (code "64") (name "Net-(R12-Pad1)") (class "Default")
      (node (ref "R12") (pin "1") (pinfunction "1_1") (pintype "passive"))
      (node (ref "XS3") (pin "9") (pinfunction "9_9") (pintype "passive"))
    )
    (net (code "65") (name "Net-(R13-Pad1)") (class "Default")
      (node (ref "R13") (pin "1") (pinfunction "1_1") (pintype "passive"))
      (node (ref "XS5") (pin "2") (pinfunction "2_2") (pintype "passive"))
    )
    (net (code "66") (name "Net-(R14-Pad1)") (class "Default")
      (node (ref "R14") (pin "1") (pinfunction "1_1") (pintype "passive"))
      (node (ref "XS5") (pin "3") (pinfunction "3_3") (pintype "passive"))
    )
    (net (code "67") (name "Net-(R15-Pad1)") (class "Default")
      (node (ref "R15") (pin "1") (pinfunction "1_1") (pintype "passive"))
      (node (ref "XS5") (pin "6") (pinfunction "6_6") (pintype "passive"))
    )
    (net (code "68") (name "Net-(VD1-C)") (class "Default")
      (node (ref "L1") (pin "1") (pinfunction "1_1") (pintype "passive"))
      (node (ref "VD1") (pin "1") (pinfunction "C_1") (pintype "passive"))
      (node (ref "VT1") (pin "3") (pinfunction "S_3") (pintype "passive"))
    )
    (net (code "69") (name "Net-(VT1-D)") (class "Default")
      (node (ref "RT1") (pin "2") (pinfunction "2_2") (pintype "passive"))
      (node (ref "VT1") (pin "2") (pinfunction "D_2") (pintype "passive"))
    )
    (net (code "70") (name "Net-(XP1-Pad1)") (class "Default")
      (node (ref "XP1") (pin "1") (pinfunction "1_1") (pintype "passive"))
      (node (ref "XS6") (pin "1") (pinfunction "1_1") (pintype "passive"))
    )
    (net (code "71") (name "Net-(XP1-Pad2)") (class "Default")
      (node (ref "XP1") (pin "2") (pinfunction "2_2") (pintype "passive"))
      (node (ref "XS6") (pin "2") (pinfunction "2_2") (pintype "passive"))
    )
    (net (code "72") (name "Net-(XP2-Pad1)") (class "Default")
      (node (ref "XP2") (pin "1") (pinfunction "1_1") (pintype "passive"))
      (node (ref "XS7") (pin "1") (pinfunction "1_1") (pintype "passive"))
    )
    (net (code "73") (name "Net-(XP2-Pad2)") (class "Default")
      (node (ref "XP2") (pin "2") (pinfunction "2_2") (pintype "passive"))
      (node (ref "XS7") (pin "2") (pinfunction "2_2") (pintype "passive"))
    )
    (net (code "74") (name "unconnected-(DA1-NC-Pad5)") (class "Default")
      (node (ref "DA1") (pin "5") (pinfunction "NC_5") (pintype "passive"))
    )
    (net (code "75") (name "unconnected-(DD1-PA2-Pad25)") (class "Default")
      (node (ref "DD1") (pin "25") (pinfunction "PA2_25") (pintype "passive"))
    )
    (net (code "76") (name "unconnected-(DD1-PA3-Pad26)") (class "Default")
      (node (ref "DD1") (pin "26") (pinfunction "PA3_26") (pintype "passive"))
    )
    (net (code "77") (name "unconnected-(DD1-PA4-Pad29)") (class "Default")
      (node (ref "DD1") (pin "29") (pinfunction "PA4_29") (pintype "passive"))
    )
    (net (code "78") (name "unconnected-(DD1-PA5-Pad30)") (class "Default")
      (node (ref "DD1") (pin "30") (pinfunction "PA5_30") (pintype "passive"))
    )
    (net (code "79") (name "unconnected-(DD1-PA6-Pad31)") (class "Default")
      (node (ref "DD1") (pin "31") (pinfunction "PA6_31") (pintype "passive"))
    )
    (net (code "80") (name "unconnected-(DD1-PA7-Pad32)") (class "Default")
      (node (ref "DD1") (pin "32") (pinfunction "PA7_32") (pintype "passive"))
    )
    (net (code "81") (name "unconnected-(DD1-PA8-Pad67)") (class "Default")
      (node (ref "DD1") (pin "67") (pinfunction "PA8_67") (pintype "passive"))
    )
    (net (code "82") (name "unconnected-(DD1-PA11-Pad70)") (class "Default")
      (node (ref "DD1") (pin "70") (pinfunction "PA11_70") (pintype "passive"))
    )
    (net (code "83") (name "unconnected-(DD1-PA12-Pad71)") (class "Default")
      (node (ref "DD1") (pin "71") (pinfunction "PA12_71") (pintype "passive"))
    )
    (net (code "84") (name "unconnected-(DD1-PA15{slash}JTDI-Pad77)") (class "Default")
      (node (ref "DD1") (pin "77") (pinfunction "PA15/JTDI_77") (pintype "passive"))
    )
    (net (code "85") (name "unconnected-(DD1-PB0-Pad35)") (class "Default")
      (node (ref "DD1") (pin "35") (pinfunction "PB0_35") (pintype "passive"))
    )
    (net (code "86") (name "unconnected-(DD1-PB1-Pad36)") (class "Default")
      (node (ref "DD1") (pin "36") (pinfunction "PB1_36") (pintype "passive"))
    )
    (net (code "87") (name "unconnected-(DD1-PB3-Pad89)") (class "Default")
      (node (ref "DD1") (pin "89") (pinfunction "PB3_89") (pintype "passive"))
    )
    (net (code "88") (name "unconnected-(DD1-PB4{slash}NJTRST-Pad90)") (class "Default")
      (node (ref "DD1") (pin "90") (pinfunction "PB4/NJTRST_90") (pintype "passive"))
    )
    (net (code "89") (name "unconnected-(DD1-PB5-Pad91)") (class "Default")
      (node (ref "DD1") (pin "91") (pinfunction "PB5_91") (pintype "passive"))
    )
    (net (code "90") (name "unconnected-(DD1-PB6-Pad92)") (class "Default")
      (node (ref "DD1") (pin "92") (pinfunction "PB6_92") (pintype "passive"))
    )
    (net (code "91") (name "unconnected-(DD1-PB7-Pad93)") (class "Default")
      (node (ref "DD1") (pin "93") (pinfunction "PB7_93") (pintype "passive"))
    )
    (net (code "92") (name "unconnected-(DD1-PB8-Pad95)") (class "Default")
      (node (ref "DD1") (pin "95") (pinfunction "PB8_95") (pintype "passive"))
    )
    (net (code "93") (name "unconnected-(DD1-PB9-Pad96)") (class "Default")
      (node (ref "DD1") (pin "96") (pinfunction "PB9_96") (pintype "passive"))
    )
    (net (code "94") (name "unconnected-(DD1-PB10-Pad47)") (class "Default")
      (node (ref "DD1") (pin "47") (pinfunction "PB10_47") (pintype "passive"))
    )
    (net (code "95") (name "unconnected-(DD1-PB11-Pad48)") (class "Default")
      (node (ref "DD1") (pin "48") (pinfunction "PB11_48") (pintype "passive"))
    )
    (net (code "96") (name "unconnected-(DD1-PB14-Pad53)") (class "Default")
      (node (ref "DD1") (pin "53") (pinfunction "PB14_53") (pintype "passive"))
    )
    (net (code "97") (name "unconnected-(DD1-PB15-Pad54)") (class "Default")
      (node (ref "DD1") (pin "54") (pinfunction "PB15_54") (pintype "passive"))
    )
    (net (code "98") (name "unconnected-(DD1-PC0-Pad15)") (class "Default")
      (node (ref "DD1") (pin "15") (pinfunction "PC0_15") (pintype "passive"))
    )
    (net (code "99") (name "unconnected-(DD1-PC1-Pad16)") (class "Default")
      (node (ref "DD1") (pin "16") (pinfunction "PC1_16") (pintype "passive"))
    )
    (net (code "100") (name "unconnected-(DD1-PC2-Pad17)") (class "Default")
      (node (ref "DD1") (pin "17") (pinfunction "PC2_17") (pintype "passive"))
    )
    (net (code "101") (name "unconnected-(DD1-PC3-Pad18)") (class "Default")
      (node (ref "DD1") (pin "18") (pinfunction "PC3_18") (pintype "passive"))
    )
    (net (code "102") (name "unconnected-(DD1-PC4-Pad33)") (class "Default")
      (node (ref "DD1") (pin "33") (pinfunction "PC4_33") (pintype "passive"))
    )
    (net (code "103") (name "unconnected-(DD1-PC5-Pad34)") (class "Default")
      (node (ref "DD1") (pin "34") (pinfunction "PC5_34") (pintype "passive"))
    )
    (net (code "104") (name "unconnected-(DD1-PC6-Pad63)") (class "Default")
      (node (ref "DD1") (pin "63") (pinfunction "PC6_63") (pintype "passive"))
    )
    (net (code "105") (name "unconnected-(DD1-PC7-Pad64)") (class "Default")
      (node (ref "DD1") (pin "64") (pinfunction "PC7_64") (pintype "passive"))
    )
    (net (code "106") (name "unconnected-(DD1-PC8-Pad65)") (class "Default")
      (node (ref "DD1") (pin "65") (pinfunction "PC8_65") (pintype "passive"))
    )
    (net (code "107") (name "unconnected-(DD1-PC9-Pad66)") (class "Default")
      (node (ref "DD1") (pin "66") (pinfunction "PC9_66") (pintype "passive"))
    )
    (net (code "108") (name "unconnected-(DD1-PC10-Pad78)") (class "Default")
      (node (ref "DD1") (pin "78") (pinfunction "PC10_78") (pintype "passive"))
    )
    (net (code "109") (name "unconnected-(DD1-PC11-Pad79)") (class "Default")
      (node (ref "DD1") (pin "79") (pinfunction "PC11_79") (pintype "passive"))
    )
    (net (code "110") (name "unconnected-(DD1-PC12-Pad80)") (class "Default")
      (node (ref "DD1") (pin "80") (pinfunction "PC12_80") (pintype "passive"))
    )
    (net (code "111") (name "unconnected-(DD1-PC13-Pad7)") (class "Default")
      (node (ref "DD1") (pin "7") (pinfunction "PC13_7") (pintype "passive"))
    )
    (net (code "112") (name "unconnected-(DD1-PC14-OSC32_IN-Pad8)") (class "Default")
      (node (ref "DD1") (pin "8") (pinfunction "PC14-OSC32_IN_8") (pintype "passive"))
    )
    (net (code "113") (name "unconnected-(DD1-PC15-OSC32_OUT-Pad9)") (class "Default")
      (node (ref "DD1") (pin "9") (pinfunction "PC15-OSC32_OUT_9") (pintype "passive"))
    )
    (net (code "114") (name "unconnected-(DD1-PD2-Pad83)") (class "Default")
      (node (ref "DD1") (pin "83") (pinfunction "PD2_83") (pintype "passive"))
    )
    (net (code "115") (name "unconnected-(DD1-PD3-Pad84)") (class "Default")
      (node (ref "DD1") (pin "84") (pinfunction "PD3_84") (pintype "passive"))
    )
    (net (code "116") (name "unconnected-(DD1-PD4-Pad85)") (class "Default")
      (node (ref "DD1") (pin "85") (pinfunction "PD4_85") (pintype "passive"))
    )
    (net (code "117") (name "unconnected-(DD1-PD5-Pad86)") (class "Default")
      (node (ref "DD1") (pin "86") (pinfunction "PD5_86") (pintype "passive"))
    )
    (net (code "118") (name "unconnected-(DD1-PD6-Pad87)") (class "Default")
      (node (ref "DD1") (pin "87") (pinfunction "PD6_87") (pintype "passive"))
    )
    (net (code "119") (name "unconnected-(DD1-PD7-Pad88)") (class "Default")
      (node (ref "DD1") (pin "88") (pinfunction "PD7_88") (pintype "passive"))
    )
    (net (code "120") (name "unconnected-(DD1-PD8-Pad55)") (class "Default")
      (node (ref "DD1") (pin "55") (pinfunction "PD8_55") (pintype "passive"))
    )
    (net (code "121") (name "unconnected-(DD1-PD9-Pad56)") (class "Default")
      (node (ref "DD1") (pin "56") (pinfunction "PD9_56") (pintype "passive"))
    )
    (net (code "122") (name "unconnected-(DD1-PD10-Pad57)") (class "Default")
      (node (ref "DD1") (pin "57") (pinfunction "PD10_57") (pintype "passive"))
    )
    (net (code "123") (name "unconnected-(DD1-PD11-Pad58)") (class "Default")
      (node (ref "DD1") (pin "58") (pinfunction "PD11_58") (pintype "passive"))
    )
    (net (code "124") (name "unconnected-(DD1-PD12-Pad59)") (class "Default")
      (node (ref "DD1") (pin "59") (pinfunction "PD12_59") (pintype "passive"))
    )
    (net (code "125") (name "unconnected-(DD1-PD13-Pad60)") (class "Default")
      (node (ref "DD1") (pin "60") (pinfunction "PD13_60") (pintype "passive"))
    )
    (net (code "126") (name "unconnected-(DD1-PD14-Pad61)") (class "Default")
      (node (ref "DD1") (pin "61") (pinfunction "PD14_61") (pintype "passive"))
    )
    (net (code "127") (name "unconnected-(DD1-PD15-Pad62)") (class "Default")
      (node (ref "DD1") (pin "62") (pinfunction "PD15_62") (pintype "passive"))
    )
    (net (code "128") (name "unconnected-(DD1-PE2-Pad1)") (class "Default")
      (node (ref "DD1") (pin "1") (pinfunction "PE2_1") (pintype "passive"))
    )
    (net (code "129") (name "unconnected-(DD1-PE3-Pad2)") (class "Default")
      (node (ref "DD1") (pin "2") (pinfunction "PE3_2") (pintype "passive"))
    )
    (net (code "130") (name "unconnected-(DD1-PE4-Pad3)") (class "Default")
      (node (ref "DD1") (pin "3") (pinfunction "PE4_3") (pintype "passive"))
    )
    (net (code "131") (name "unconnected-(DD1-PE5-Pad4)") (class "Default")
      (node (ref "DD1") (pin "4") (pinfunction "PE5_4") (pintype "passive"))
    )
    (net (code "132") (name "unconnected-(DD1-PE6-Pad5)") (class "Default")
      (node (ref "DD1") (pin "5") (pinfunction "PE6_5") (pintype "passive"))
    )
    (net (code "133") (name "unconnected-(DD1-PE7-Pad38)") (class "Default")
      (node (ref "DD1") (pin "38") (pinfunction "PE7_38") (pintype "passive"))
    )
    (net (code "134") (name "unconnected-(DD1-PE8-Pad39)") (class "Default")
      (node (ref "DD1") (pin "39") (pinfunction "PE8_39") (pintype "passive"))
    )
    (net (code "135") (name "unconnected-(DD1-PE9-Pad40)") (class "Default")
      (node (ref "DD1") (pin "40") (pinfunction "PE9_40") (pintype "passive"))
    )
    (net (code "136") (name "unconnected-(DD1-PE10-Pad41)") (class "Default")
      (node (ref "DD1") (pin "41") (pinfunction "PE10_41") (pintype "passive"))
    )
    (net (code "137") (name "unconnected-(DD1-PE11-Pad42)") (class "Default")
      (node (ref "DD1") (pin "42") (pinfunction "PE11_42") (pintype "passive"))
    )
    (net (code "138") (name "unconnected-(DD1-PE12-Pad43)") (class "Default")
      (node (ref "DD1") (pin "43") (pinfunction "PE12_43") (pintype "passive"))
    )
    (net (code "139") (name "unconnected-(DD1-PE13-Pad44)") (class "Default")
      (node (ref "DD1") (pin "44") (pinfunction "PE13_44") (pintype "passive"))
    )
    (net (code "140") (name "unconnected-(DD1-PE15-Pad46)") (class "Default")
      (node (ref "DD1") (pin "46") (pinfunction "PE15_46") (pintype "passive"))
    )
    (net (code "141") (name "unconnected-(XS1-Pad3)") (class "Default")
      (node (ref "XS1") (pin "3") (pinfunction "3_3") (pintype "passive"))
    )
    (net (code "142") (name "unconnected-(XS1-Pad5)") (class "Default")
      (node (ref "XS1") (pin "5") (pinfunction "5_5") (pintype "passive"))
    )
    (net (code "143") (name "unconnected-(XS1-Pad6)") (class "Default")
      (node (ref "XS1") (pin "6") (pinfunction "6_6") (pintype "passive"))
    )
    (net (code "144") (name "unconnected-(XS1-Pad7)") (class "Default")
      (node (ref "XS1") (pin "7") (pinfunction "7_7") (pintype "passive"))
    )
    (net (code "145") (name "unconnected-(XS1-Pad11)") (class "Default")
      (node (ref "XS1") (pin "11") (pinfunction "11_11") (pintype "passive"))
    )
    (net (code "146") (name "unconnected-(XS1-Pad13)") (class "Default")
      (node (ref "XS1") (pin "13") (pinfunction "13_13") (pintype "passive"))
    )
    (net (code "147") (name "unconnected-(XS1-Pad16)") (class "Default")
      (node (ref "XS1") (pin "16") (pinfunction "16_16") (pintype "passive"))
    )
    (net (code "148") (name "unconnected-(XS1-Pad17)") (class "Default")
      (node (ref "XS1") (pin "17") (pinfunction "17_17") (pintype "passive"))
    )
    (net (code "149") (name "unconnected-(XS1-Pad19)") (class "Default")
      (node (ref "XS1") (pin "19") (pinfunction "19_19") (pintype "passive"))
    )
    (net (code "150") (name "unconnected-(XS1-Pad23)") (class "Default")
      (node (ref "XS1") (pin "23") (pinfunction "23_23") (pintype "passive"))
    )
    (net (code "151") (name "unconnected-(XS1-Pad24)") (class "Default")
      (node (ref "XS1") (pin "24") (pinfunction "24_24") (pintype "passive"))
    )
    (net (code "152") (name "unconnected-(XS1-Pad25)") (class "Default")
      (node (ref "XS1") (pin "25") (pinfunction "25_25") (pintype "passive"))
    )
    (net (code "153") (name "unconnected-(XS1-Pad28)") (class "Default")
      (node (ref "XS1") (pin "28") (pinfunction "28_28") (pintype "passive"))
    )
    (net (code "154") (name "unconnected-(XS1-Pad30)") (class "Default")
      (node (ref "XS1") (pin "30") (pinfunction "30_30") (pintype "passive"))
    )
    (net (code "155") (name "unconnected-(XS1-Pad31)") (class "Default")
      (node (ref "XS1") (pin "31") (pinfunction "31_31") (pintype "passive"))
    )
    (net (code "156") (name "unconnected-(XS1-Pad32)") (class "Default")
      (node (ref "XS1") (pin "32") (pinfunction "32_32") (pintype "passive"))
    )
    (net (code "157") (name "unconnected-(XS1-Pad33)") (class "Default")
      (node (ref "XS1") (pin "33") (pinfunction "33_33") (pintype "passive"))
    )
    (net (code "158") (name "unconnected-(XS1-Pad44)") (class "Default")
      (node (ref "XS1") (pin "44") (pinfunction "44_44") (pintype "passive"))
    )
    (net (code "159") (name "unconnected-(XS1-Pad45)") (class "Default")
      (node (ref "XS1") (pin "45") (pinfunction "45_45") (pintype "passive"))
    )
    (net (code "160") (name "unconnected-(XS1-Pad46)") (class "Default")
      (node (ref "XS1") (pin "46") (pinfunction "46_46") (pintype "passive"))
    )
    (net (code "161") (name "unconnected-(XS1-Pad47)") (class "Default")
      (node (ref "XS1") (pin "47") (pinfunction "47_47") (pintype "passive"))
    )
    (net (code "162") (name "unconnected-(XS1-Pad48)") (class "Default")
      (node (ref "XS1") (pin "48") (pinfunction "48_48") (pintype "passive"))
    )
    (net (code "163") (name "unconnected-(XS1-Pad49)") (class "Default")
      (node (ref "XS1") (pin "49") (pinfunction "49_49") (pintype "passive"))
    )
    (net (code "164") (name "unconnected-(XS1-Pad51)") (class "Default")
      (node (ref "XS1") (pin "51") (pinfunction "51_51") (pintype "passive"))
    )
    (net (code "165") (name "unconnected-(XS5-Pad5)") (class "Default")
      (node (ref "XS5") (pin "5") (pinfunction "5_5") (pintype "passive"))
    )
    (net (code "166") (name "unconnected-(XS5-Pad7)") (class "Default")
      (node (ref "XS5") (pin "7") (pinfunction "7_7") (pintype "passive"))
    )
  )
)
